# pwr.net
KiCad netlist of a schematic drawn in Altium Designer
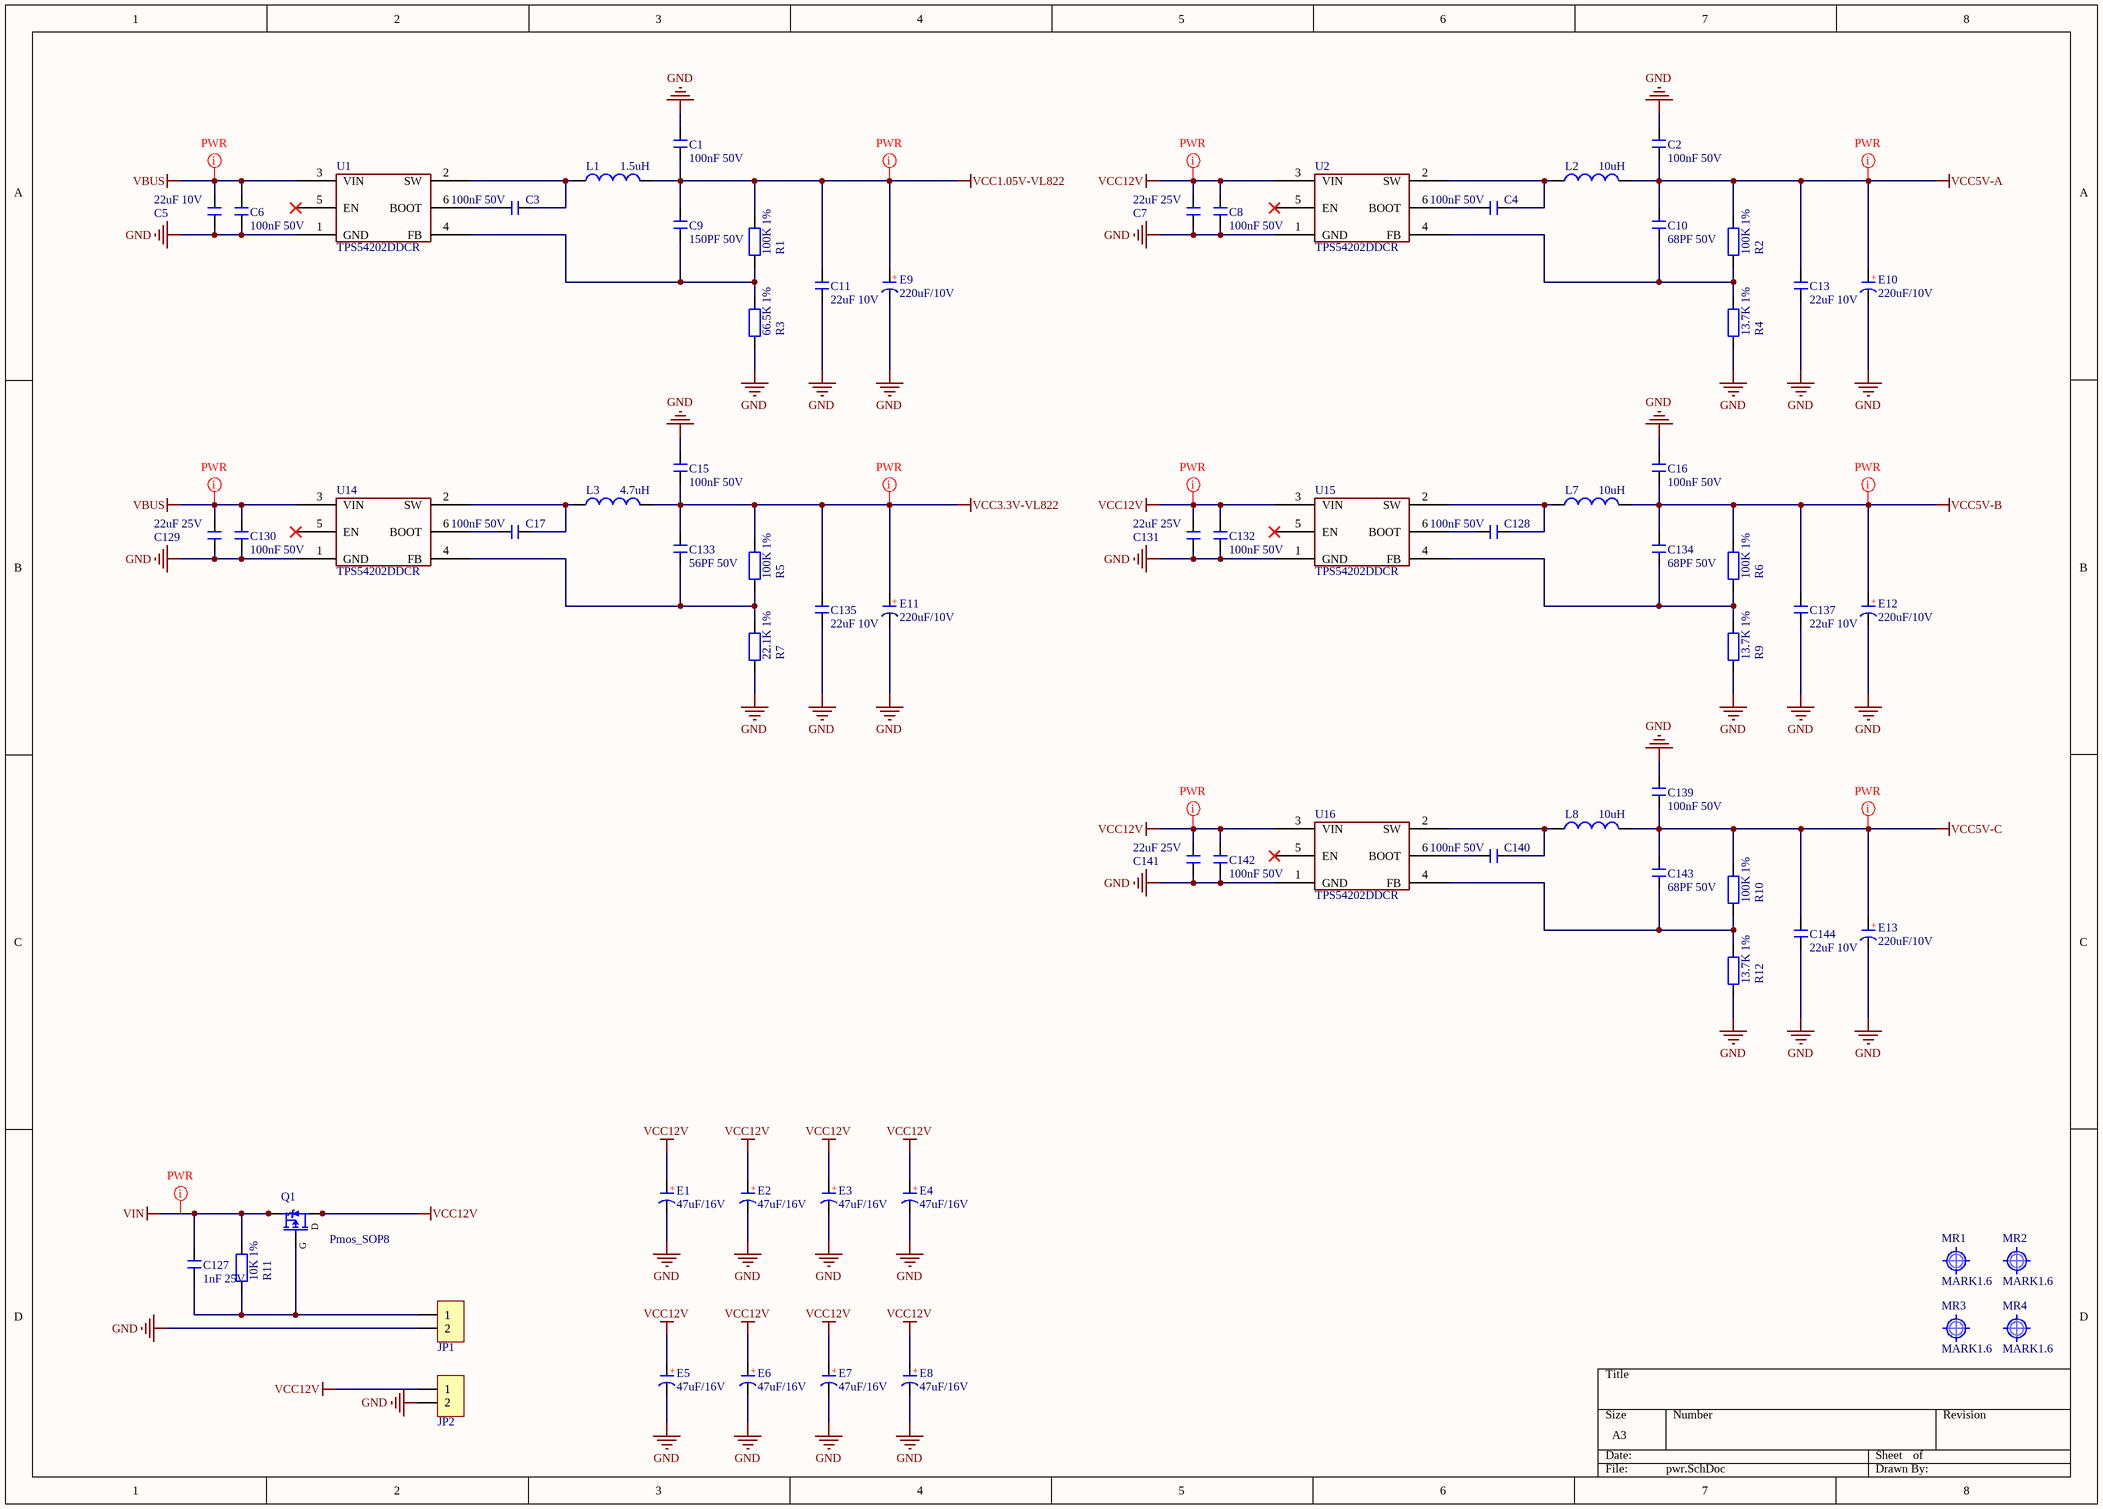
[diagram p0: pwr.SchDoc]

(export (version "E")
  (design (tool "Eeschema 10.0.6"))
  (components
    (comp (ref "C1")
      (value "100nF 50V")
      (footprint "C0402_L")
      (description "无极性贴片电容")
      (fields (field (name "版权归属") "源创客"))
      (libsource (lib "Capacitor") (part "C"))
    )
    (comp (ref "C2")
      (value "100nF 50V")
      (footprint "C0402_L")
      (description "无极性贴片电容")
      (fields (field (name "版权归属") "源创客"))
      (libsource (lib "Capacitor") (part "C"))
    )
    (comp (ref "C3")
      (value "100nF 50V")
      (footprint "C0402_L")
      (description "无极性贴片电容")
      (fields (field (name "版权归属") "源创客"))
      (libsource (lib "Capacitor") (part "C"))
    )
    (comp (ref "C4")
      (value "100nF 50V")
      (footprint "C0402_L")
      (description "无极性贴片电容")
      (fields (field (name "版权归属") "源创客"))
      (libsource (lib "Capacitor") (part "C"))
    )
    (comp (ref "C5")
      (value "22uF 10V")
      (footprint "C0805_L")
      (description "无极性贴片电容")
      (fields (field (name "版权归属") "源创客"))
      (libsource (lib "Capacitor") (part "C"))
    )
    (comp (ref "C6")
      (value "100nF 50V")
      (footprint "C0402_L")
      (description "无极性贴片电容")
      (fields (field (name "版权归属") "源创客"))
      (libsource (lib "Capacitor") (part "C"))
    )
    (comp (ref "C7")
      (value "22uF 25V")
      (footprint "C0805_L")
      (description "无极性贴片电容")
      (fields (field (name "版权归属") "源创客"))
      (libsource (lib "Capacitor") (part "C"))
    )
    (comp (ref "C8")
      (value "100nF 50V")
      (footprint "C0402_L")
      (description "无极性贴片电容")
      (fields (field (name "版权归属") "源创客"))
      (libsource (lib "Capacitor") (part "C"))
    )
    (comp (ref "C9")
      (value "150PF 50V")
      (footprint "C0402_L")
      (description "无极性贴片电容")
      (fields (field (name "版权归属") "源创客"))
      (libsource (lib "Capacitor") (part "C"))
    )
    (comp (ref "C10")
      (value "68PF 50V")
      (footprint "C0402_L")
      (description "无极性贴片电容")
      (fields (field (name "版权归属") "源创客"))
      (libsource (lib "Capacitor") (part "C"))
    )
    (comp (ref "C11")
      (value "22uF 10V")
      (footprint "C0603_L")
      (description "无极性贴片电容")
      (fields (field (name "版权归属") "源创客"))
      (libsource (lib "Capacitor") (part "C"))
    )
    (comp (ref "C13")
      (value "22uF 10V")
      (footprint "C0603_L")
      (description "无极性贴片电容")
      (fields (field (name "版权归属") "源创客"))
      (libsource (lib "Capacitor") (part "C"))
    )
    (comp (ref "C15")
      (value "100nF 50V")
      (footprint "C0402_L")
      (description "无极性贴片电容")
      (fields (field (name "版权归属") "源创客"))
      (libsource (lib "Capacitor") (part "C"))
    )
    (comp (ref "C16")
      (value "100nF 50V")
      (footprint "C0402_L")
      (description "无极性贴片电容")
      (fields (field (name "版权归属") "源创客"))
      (libsource (lib "Capacitor") (part "C"))
    )
    (comp (ref "C17")
      (value "100nF 50V")
      (footprint "C0402_L")
      (description "无极性贴片电容")
      (fields (field (name "版权归属") "源创客"))
      (libsource (lib "Capacitor") (part "C"))
    )
    (comp (ref "C127")
      (value "1nF 25V")
      (footprint "C0402_L")
      (description "无极性贴片电容")
      (fields (field (name "版权归属") "源创客"))
      (libsource (lib "Capacitor") (part "C"))
    )
    (comp (ref "C128")
      (value "100nF 50V")
      (footprint "C0402_L")
      (description "无极性贴片电容")
      (fields (field (name "版权归属") "源创客"))
      (libsource (lib "Capacitor") (part "C"))
    )
    (comp (ref "C129")
      (value "22uF 25V")
      (footprint "C0805_L")
      (description "无极性贴片电容")
      (fields (field (name "版权归属") "源创客"))
      (libsource (lib "Capacitor") (part "C"))
    )
    (comp (ref "C130")
      (value "100nF 50V")
      (footprint "C0402_L")
      (description "无极性贴片电容")
      (fields (field (name "版权归属") "源创客"))
      (libsource (lib "Capacitor") (part "C"))
    )
    (comp (ref "C131")
      (value "22uF 25V")
      (footprint "C0805_L")
      (description "无极性贴片电容")
      (fields (field (name "版权归属") "源创客"))
      (libsource (lib "Capacitor") (part "C"))
    )
    (comp (ref "C132")
      (value "100nF 50V")
      (footprint "C0402_L")
      (description "无极性贴片电容")
      (fields (field (name "版权归属") "源创客"))
      (libsource (lib "Capacitor") (part "C"))
    )
    (comp (ref "C133")
      (value "56PF 50V")
      (footprint "C0402_L")
      (description "无极性贴片电容")
      (fields (field (name "版权归属") "源创客"))
      (libsource (lib "Capacitor") (part "C"))
    )
    (comp (ref "C134")
      (value "68PF 50V")
      (footprint "C0402_L")
      (description "无极性贴片电容")
      (fields (field (name "版权归属") "源创客"))
      (libsource (lib "Capacitor") (part "C"))
    )
    (comp (ref "C135")
      (value "22uF 10V")
      (footprint "C0603_L")
      (description "无极性贴片电容")
      (fields (field (name "版权归属") "源创客"))
      (libsource (lib "Capacitor") (part "C"))
    )
    (comp (ref "C137")
      (value "22uF 10V")
      (footprint "C0603_L")
      (description "无极性贴片电容")
      (fields (field (name "版权归属") "源创客"))
      (libsource (lib "Capacitor") (part "C"))
    )
    (comp (ref "C139")
      (value "100nF 50V")
      (footprint "C0402_L")
      (description "无极性贴片电容")
      (fields (field (name "版权归属") "源创客"))
      (libsource (lib "Capacitor") (part "C"))
    )
    (comp (ref "C140")
      (value "100nF 50V")
      (footprint "C0402_L")
      (description "无极性贴片电容")
      (fields (field (name "版权归属") "源创客"))
      (libsource (lib "Capacitor") (part "C"))
    )
    (comp (ref "C141")
      (value "22uF 25V")
      (footprint "C0805_L")
      (description "无极性贴片电容")
      (fields (field (name "版权归属") "源创客"))
      (libsource (lib "Capacitor") (part "C"))
    )
    (comp (ref "C142")
      (value "100nF 50V")
      (footprint "C0402_L")
      (description "无极性贴片电容")
      (fields (field (name "版权归属") "源创客"))
      (libsource (lib "Capacitor") (part "C"))
    )
    (comp (ref "C143")
      (value "68PF 50V")
      (footprint "C0402_L")
      (description "无极性贴片电容")
      (fields (field (name "版权归属") "源创客"))
      (libsource (lib "Capacitor") (part "C"))
    )
    (comp (ref "C144")
      (value "22uF 10V")
      (footprint "C0603_L")
      (description "无极性贴片电容")
      (fields (field (name "版权归属") "源创客"))
      (libsource (lib "Capacitor") (part "C"))
    )
    (comp (ref "E1")
      (value "47uF/16V")
      (footprint "CS 6*4 - R")
      (description "贴片电解电容")
      (fields (field (name "版权归属") "源创客"))
      (libsource (lib "Capacitor") (part "C-CD"))
    )
    (comp (ref "E2")
      (value "47uF/16V")
      (footprint "CS 6*4 - R")
      (description "贴片电解电容")
      (fields (field (name "版权归属") "源创客"))
      (libsource (lib "Capacitor") (part "C-CD"))
    )
    (comp (ref "E3")
      (value "47uF/16V")
      (footprint "CS 6*4 - R")
      (description "贴片电解电容")
      (fields (field (name "版权归属") "源创客"))
      (libsource (lib "Capacitor") (part "C-CD"))
    )
    (comp (ref "E4")
      (value "47uF/16V")
      (footprint "CS 6*4 - R")
      (description "贴片电解电容")
      (fields (field (name "版权归属") "源创客"))
      (libsource (lib "Capacitor") (part "C-CD"))
    )
    (comp (ref "E5")
      (value "47uF/16V")
      (footprint "CS 6*4 - R")
      (description "贴片电解电容")
      (fields (field (name "版权归属") "源创客"))
      (libsource (lib "Capacitor") (part "C-CD"))
    )
    (comp (ref "E6")
      (value "47uF/16V")
      (footprint "CS 6*4 - R")
      (description "贴片电解电容")
      (fields (field (name "版权归属") "源创客"))
      (libsource (lib "Capacitor") (part "C-CD"))
    )
    (comp (ref "E7")
      (value "47uF/16V")
      (footprint "CS 6*4 - R")
      (description "贴片电解电容")
      (fields (field (name "版权归属") "源创客"))
      (libsource (lib "Capacitor") (part "C-CD"))
    )
    (comp (ref "E8")
      (value "47uF/16V")
      (footprint "CS 6*4 - R")
      (description "贴片电解电容")
      (fields (field (name "版权归属") "源创客"))
      (libsource (lib "Capacitor") (part "C-CD"))
    )
    (comp (ref "E9")
      (value "220uF/10V")
      (footprint "CS 6*4 - B")
      (description "贴片电解电容")
      (fields (field (name "版权归属") "源创客"))
      (libsource (lib "Capacitor") (part "C-CD"))
    )
    (comp (ref "E10")
      (value "220uF/10V")
      (footprint "CS 6*4 - B")
      (description "贴片电解电容")
      (fields (field (name "版权归属") "源创客"))
      (libsource (lib "Capacitor") (part "C-CD"))
    )
    (comp (ref "E11")
      (value "220uF/10V")
      (footprint "CS 6*4 - B")
      (description "贴片电解电容")
      (fields (field (name "版权归属") "源创客"))
      (libsource (lib "Capacitor") (part "C-CD"))
    )
    (comp (ref "E12")
      (value "220uF/10V")
      (footprint "CS 6*4 - B")
      (description "贴片电解电容")
      (fields (field (name "版权归属") "源创客"))
      (libsource (lib "Capacitor") (part "C-CD"))
    )
    (comp (ref "E13")
      (value "220uF/10V")
      (footprint "CS 6*4 - B")
      (description "贴片电解电容")
      (fields (field (name "版权归属") "源创客"))
      (libsource (lib "Capacitor") (part "C-CD"))
    )
    (comp (ref "JP1")
      (value "HDR-1X2")
      (footprint "ZH1.5-WS-2P")
      (description "2P接插件")
      (fields (field (name "版权归属") "源创客"))
      (libsource (lib "Connector-PinHeader") (part "Header 2"))
    )
    (comp (ref "JP2")
      (value "HDR-1X2")
      (footprint "XH2.54-WS-2P")
      (description "2P接插件")
      (fields (field (name "版权归属") "源创客"))
      (libsource (lib "Connector-PinHeader") (part "Header 2"))
    )
    (comp (ref "L1")
      (value "1.5uH")
      (footprint "SMMS0420")
      (description "小功率贴片电感")
      (fields (field (name "版权归属") "源创客"))
      (libsource (lib "Inductor") (part "L"))
    )
    (comp (ref "L2")
      (value "10uH")
      (footprint "SMMS0420")
      (description "小功率贴片电感")
      (fields (field (name "版权归属") "源创客"))
      (libsource (lib "Inductor") (part "L"))
    )
    (comp (ref "L3")
      (value "4.7uH")
      (footprint "SMMS0420")
      (description "小功率贴片电感")
      (fields (field (name "版权归属") "源创客"))
      (libsource (lib "Inductor") (part "L"))
    )
    (comp (ref "L7")
      (value "10uH")
      (footprint "SMMS0420")
      (description "小功率贴片电感")
      (fields (field (name "版权归属") "源创客"))
      (libsource (lib "Inductor") (part "L"))
    )
    (comp (ref "L8")
      (value "10uH")
      (footprint "SMMS0420")
      (description "小功率贴片电感")
      (fields (field (name "版权归属") "源创客"))
      (libsource (lib "Inductor") (part "L"))
    )
    (comp (ref "MR1")
      (value "MARK1.6")
      (footprint "Mark 1")
      (description "光学定位点")
      (fields (field (name "版权归属") "源创客"))
      (libsource (lib "Hole") (part "MARK"))
    )
    (comp (ref "MR2")
      (value "MARK1.6")
      (footprint "Mark 1")
      (description "光学定位点")
      (fields (field (name "版权归属") "源创客"))
      (libsource (lib "Hole") (part "MARK"))
    )
    (comp (ref "MR3")
      (value "MARK1.6")
      (footprint "Mark 1")
      (description "光学定位点")
      (fields (field (name "版权归属") "源创客"))
      (libsource (lib "Hole") (part "MARK"))
    )
    (comp (ref "MR4")
      (value "MARK1.6")
      (footprint "Mark 1")
      (description "光学定位点")
      (fields (field (name "版权归属") "源创客"))
      (libsource (lib "Hole") (part "MARK"))
    )
    (comp (ref "Q1")
      (value "Pmos_SOP8")
      (footprint "SOP8_L")
      (fields (field (name "版权归属") "源创客"))
      (libsource (lib "MOSFET BJT IGBT") (part "Pmos_SOP8"))
    )
    (comp (ref "R1")
      (value "100K 1%")
      (footprint "R0402_L")
      (description "贴片电阻")
      (fields (field (name "版权归属") "源创客"))
      (libsource (lib "Resistor") (part "R"))
    )
    (comp (ref "R2")
      (value "100K 1%")
      (footprint "R0402_L")
      (description "贴片电阻")
      (fields (field (name "版权归属") "源创客"))
      (libsource (lib "Resistor") (part "R"))
    )
    (comp (ref "R3")
      (value "66.5K 1%")
      (footprint "R0402_L")
      (description "贴片电阻")
      (fields (field (name "版权归属") "源创客"))
      (libsource (lib "Resistor") (part "R"))
    )
    (comp (ref "R4")
      (value "13.7K 1%")
      (footprint "R0402_L")
      (description "贴片电阻")
      (fields (field (name "版权归属") "源创客"))
      (libsource (lib "Resistor") (part "R"))
    )
    (comp (ref "R5")
      (value "100K 1%")
      (footprint "R0402_L")
      (description "贴片电阻")
      (fields (field (name "版权归属") "源创客"))
      (libsource (lib "Resistor") (part "R"))
    )
    (comp (ref "R6")
      (value "100K 1%")
      (footprint "R0402_L")
      (description "贴片电阻")
      (fields (field (name "版权归属") "源创客"))
      (libsource (lib "Resistor") (part "R"))
    )
    (comp (ref "R7")
      (value "22.1K 1%")
      (footprint "R0402_L")
      (description "贴片电阻")
      (fields (field (name "版权归属") "源创客"))
      (libsource (lib "Resistor") (part "R"))
    )
    (comp (ref "R9")
      (value "13.7K 1%")
      (footprint "R0402_L")
      (description "贴片电阻")
      (fields (field (name "版权归属") "源创客"))
      (libsource (lib "Resistor") (part "R"))
    )
    (comp (ref "R10")
      (value "100K 1%")
      (footprint "R0402_L")
      (description "贴片电阻")
      (fields (field (name "版权归属") "源创客"))
      (libsource (lib "Resistor") (part "R"))
    )
    (comp (ref "R11")
      (value "10K 1%")
      (footprint "R0402_L")
      (description "贴片电阻")
      (fields (field (name "版权归属") "源创客"))
      (libsource (lib "Resistor") (part "R"))
    )
    (comp (ref "R12")
      (value "13.7K 1%")
      (footprint "R0402_L")
      (description "贴片电阻")
      (fields (field (name "版权归属") "源创客"))
      (libsource (lib "Resistor") (part "R"))
    )
    (comp (ref "U1")
      (value "TPS54202DDCR")
      (footprint "SOT23-6L")
      (description "DCDC Convert")
      (libsource (lib "DCDC Convert") (part "TPS54202DDCR"))
    )
    (comp (ref "U2")
      (value "TPS54202DDCR")
      (footprint "SOT23-6L")
      (description "DCDC Convert")
      (libsource (lib "DCDC Convert") (part "TPS54202DDCR"))
    )
    (comp (ref "U14")
      (value "TPS54202DDCR")
      (footprint "SOT23-6L")
      (description "DCDC Convert")
      (libsource (lib "DCDC Convert") (part "TPS54202DDCR"))
    )
    (comp (ref "U15")
      (value "TPS54202DDCR")
      (footprint "SOT23-6L")
      (description "DCDC Convert")
      (libsource (lib "DCDC Convert") (part "TPS54202DDCR"))
    )
    (comp (ref "U16")
      (value "TPS54202DDCR")
      (footprint "SOT23-6L")
      (description "DCDC Convert")
      (libsource (lib "DCDC Convert") (part "TPS54202DDCR"))
    )
  )
  (nets
    (net (code "1") (name "GND") (class "Default")
      (node (ref "C1") (pin "2") (pinfunction "2_2") (pintype "passive"))
      (node (ref "C11") (pin "2") (pinfunction "2_2") (pintype "passive"))
      (node (ref "C129") (pin "1") (pinfunction "1_1") (pintype "passive"))
      (node (ref "C13") (pin "2") (pinfunction "2_2") (pintype "passive"))
      (node (ref "C130") (pin "1") (pinfunction "1_1") (pintype "passive"))
      (node (ref "C131") (pin "1") (pinfunction "1_1") (pintype "passive"))
      (node (ref "C132") (pin "1") (pinfunction "1_1") (pintype "passive"))
      (node (ref "C135") (pin "2") (pinfunction "2_2") (pintype "passive"))
      (node (ref "C137") (pin "2") (pinfunction "2_2") (pintype "passive"))
      (node (ref "C139") (pin "2") (pinfunction "2_2") (pintype "passive"))
      (node (ref "C141") (pin "1") (pinfunction "1_1") (pintype "passive"))
      (node (ref "C142") (pin "1") (pinfunction "1_1") (pintype "passive"))
      (node (ref "C144") (pin "2") (pinfunction "2_2") (pintype "passive"))
      (node (ref "C15") (pin "2") (pinfunction "2_2") (pintype "passive"))
      (node (ref "C16") (pin "2") (pinfunction "2_2") (pintype "passive"))
      (node (ref "C2") (pin "2") (pinfunction "2_2") (pintype "passive"))
      (node (ref "C5") (pin "1") (pinfunction "1_1") (pintype "passive"))
      (node (ref "C6") (pin "1") (pinfunction "1_1") (pintype "passive"))
      (node (ref "C7") (pin "1") (pinfunction "1_1") (pintype "passive"))
      (node (ref "C8") (pin "1") (pinfunction "1_1") (pintype "passive"))
      (node (ref "E1") (pin "2") (pinfunction "K_2") (pintype "passive"))
      (node (ref "E10") (pin "2") (pinfunction "K_2") (pintype "passive"))
      (node (ref "E11") (pin "2") (pinfunction "K_2") (pintype "passive"))
      (node (ref "E12") (pin "2") (pinfunction "K_2") (pintype "passive"))
      (node (ref "E13") (pin "2") (pinfunction "K_2") (pintype "passive"))
      (node (ref "E2") (pin "2") (pinfunction "K_2") (pintype "passive"))
      (node (ref "E3") (pin "2") (pinfunction "K_2") (pintype "passive"))
      (node (ref "E4") (pin "2") (pinfunction "K_2") (pintype "passive"))
      (node (ref "E5") (pin "2") (pinfunction "K_2") (pintype "passive"))
      (node (ref "E6") (pin "2") (pinfunction "K_2") (pintype "passive"))
      (node (ref "E7") (pin "2") (pinfunction "K_2") (pintype "passive"))
      (node (ref "E8") (pin "2") (pinfunction "K_2") (pintype "passive"))
      (node (ref "E9") (pin "2") (pinfunction "K_2") (pintype "passive"))
      (node (ref "JP1") (pin "2") (pinfunction "2_2") (pintype "passive"))
      (node (ref "JP2") (pin "2") (pinfunction "2_2") (pintype "passive"))
      (node (ref "R12") (pin "2") (pinfunction "2_2") (pintype "passive"))
      (node (ref "R3") (pin "2") (pinfunction "2_2") (pintype "passive"))
      (node (ref "R4") (pin "2") (pinfunction "2_2") (pintype "passive"))
      (node (ref "R7") (pin "2") (pinfunction "2_2") (pintype "passive"))
      (node (ref "R9") (pin "2") (pinfunction "2_2") (pintype "passive"))
      (node (ref "U1") (pin "1") (pinfunction "GND_1") (pintype "passive"))
      (node (ref "U14") (pin "1") (pinfunction "GND_1") (pintype "passive"))
      (node (ref "U15") (pin "1") (pinfunction "GND_1") (pintype "passive"))
      (node (ref "U16") (pin "1") (pinfunction "GND_1") (pintype "passive"))
      (node (ref "U2") (pin "1") (pinfunction "GND_1") (pintype "passive"))
    )
    (net (code "2") (name "Net-(Q1-G)") (class "Default")
      (node (ref "C127") (pin "2") (pinfunction "2_2") (pintype "passive"))
      (node (ref "JP1") (pin "1") (pinfunction "1_1") (pintype "passive"))
      (node (ref "Q1") (pin "4") (pinfunction "G_4") (pintype "passive"))
      (node (ref "R11") (pin "2") (pinfunction "2_2") (pintype "passive"))
    )
    (net (code "3") (name "Net-(U1-BOOT)") (class "Default")
      (node (ref "C3") (pin "1") (pinfunction "1_1") (pintype "passive"))
      (node (ref "U1") (pin "6") (pinfunction "BOOT_6") (pintype "passive"))
    )
    (net (code "4") (name "Net-(U1-FB)") (class "Default")
      (node (ref "C9") (pin "1") (pinfunction "1_1") (pintype "passive"))
      (node (ref "R1") (pin "2") (pinfunction "2_2") (pintype "passive"))
      (node (ref "R3") (pin "1") (pinfunction "1_1") (pintype "passive"))
      (node (ref "U1") (pin "4") (pinfunction "FB_4") (pintype "passive"))
    )
    (net (code "5") (name "Net-(U1-SW)") (class "Default")
      (node (ref "C3") (pin "2") (pinfunction "2_2") (pintype "passive"))
      (node (ref "L1") (pin "1") (pinfunction "1_1") (pintype "passive"))
      (node (ref "U1") (pin "2") (pinfunction "SW_2") (pintype "passive"))
    )
    (net (code "6") (name "Net-(U2-BOOT)") (class "Default")
      (node (ref "C4") (pin "1") (pinfunction "1_1") (pintype "passive"))
      (node (ref "U2") (pin "6") (pinfunction "BOOT_6") (pintype "passive"))
    )
    (net (code "7") (name "Net-(U2-FB)") (class "Default")
      (node (ref "C10") (pin "1") (pinfunction "1_1") (pintype "passive"))
      (node (ref "R2") (pin "2") (pinfunction "2_2") (pintype "passive"))
      (node (ref "R4") (pin "1") (pinfunction "1_1") (pintype "passive"))
      (node (ref "U2") (pin "4") (pinfunction "FB_4") (pintype "passive"))
    )
    (net (code "8") (name "Net-(U2-SW)") (class "Default")
      (node (ref "C4") (pin "2") (pinfunction "2_2") (pintype "passive"))
      (node (ref "L2") (pin "1") (pinfunction "1_1") (pintype "passive"))
      (node (ref "U2") (pin "2") (pinfunction "SW_2") (pintype "passive"))
    )
    (net (code "9") (name "Net-(U14-BOOT)") (class "Default")
      (node (ref "C17") (pin "1") (pinfunction "1_1") (pintype "passive"))
      (node (ref "U14") (pin "6") (pinfunction "BOOT_6") (pintype "passive"))
    )
    (net (code "10") (name "Net-(U14-FB)") (class "Default")
      (node (ref "C133") (pin "1") (pinfunction "1_1") (pintype "passive"))
      (node (ref "R5") (pin "2") (pinfunction "2_2") (pintype "passive"))
      (node (ref "R7") (pin "1") (pinfunction "1_1") (pintype "passive"))
      (node (ref "U14") (pin "4") (pinfunction "FB_4") (pintype "passive"))
    )
    (net (code "11") (name "Net-(U14-SW)") (class "Default")
      (node (ref "C17") (pin "2") (pinfunction "2_2") (pintype "passive"))
      (node (ref "L3") (pin "1") (pinfunction "1_1") (pintype "passive"))
      (node (ref "U14") (pin "2") (pinfunction "SW_2") (pintype "passive"))
    )
    (net (code "12") (name "Net-(U15-BOOT)") (class "Default")
      (node (ref "C128") (pin "1") (pinfunction "1_1") (pintype "passive"))
      (node (ref "U15") (pin "6") (pinfunction "BOOT_6") (pintype "passive"))
    )
    (net (code "13") (name "Net-(U15-FB)") (class "Default")
      (node (ref "C134") (pin "1") (pinfunction "1_1") (pintype "passive"))
      (node (ref "R6") (pin "2") (pinfunction "2_2") (pintype "passive"))
      (node (ref "R9") (pin "1") (pinfunction "1_1") (pintype "passive"))
      (node (ref "U15") (pin "4") (pinfunction "FB_4") (pintype "passive"))
    )
    (net (code "14") (name "Net-(U15-SW)") (class "Default")
      (node (ref "C128") (pin "2") (pinfunction "2_2") (pintype "passive"))
      (node (ref "L7") (pin "1") (pinfunction "1_1") (pintype "passive"))
      (node (ref "U15") (pin "2") (pinfunction "SW_2") (pintype "passive"))
    )
    (net (code "15") (name "Net-(U16-BOOT)") (class "Default")
      (node (ref "C140") (pin "1") (pinfunction "1_1") (pintype "passive"))
      (node (ref "U16") (pin "6") (pinfunction "BOOT_6") (pintype "passive"))
    )
    (net (code "16") (name "Net-(U16-FB)") (class "Default")
      (node (ref "C143") (pin "1") (pinfunction "1_1") (pintype "passive"))
      (node (ref "R10") (pin "2") (pinfunction "2_2") (pintype "passive"))
      (node (ref "R12") (pin "1") (pinfunction "1_1") (pintype "passive"))
      (node (ref "U16") (pin "4") (pinfunction "FB_4") (pintype "passive"))
    )
    (net (code "17") (name "Net-(U16-SW)") (class "Default")
      (node (ref "C140") (pin "2") (pinfunction "2_2") (pintype "passive"))
      (node (ref "L8") (pin "1") (pinfunction "1_1") (pintype "passive"))
      (node (ref "U16") (pin "2") (pinfunction "SW_2") (pintype "passive"))
    )
    (net (code "18") (name "VBUS") (class "Default")
      (node (ref "C129") (pin "2") (pinfunction "2_2") (pintype "passive"))
      (node (ref "C130") (pin "2") (pinfunction "2_2") (pintype "passive"))
      (node (ref "C5") (pin "2") (pinfunction "2_2") (pintype "passive"))
      (node (ref "C6") (pin "2") (pinfunction "2_2") (pintype "passive"))
      (node (ref "U1") (pin "3") (pinfunction "VIN_3") (pintype "passive"))
      (node (ref "U14") (pin "3") (pinfunction "VIN_3") (pintype "passive"))
    )
    (net (code "19") (name "VCC1.05V-VL822") (class "Default")
      (node (ref "C1") (pin "1") (pinfunction "1_1") (pintype "passive"))
      (node (ref "C11") (pin "1") (pinfunction "1_1") (pintype "passive"))
      (node (ref "C9") (pin "2") (pinfunction "2_2") (pintype "passive"))
      (node (ref "E9") (pin "1") (pinfunction "A_1") (pintype "passive"))
      (node (ref "L1") (pin "2") (pinfunction "2_2") (pintype "passive"))
      (node (ref "R1") (pin "1") (pinfunction "1_1") (pintype "passive"))
    )
    (net (code "20") (name "VCC3.3V-VL822") (class "Default")
      (node (ref "C133") (pin "2") (pinfunction "2_2") (pintype "passive"))
      (node (ref "C135") (pin "1") (pinfunction "1_1") (pintype "passive"))
      (node (ref "C15") (pin "1") (pinfunction "1_1") (pintype "passive"))
      (node (ref "E11") (pin "1") (pinfunction "A_1") (pintype "passive"))
      (node (ref "L3") (pin "2") (pinfunction "2_2") (pintype "passive"))
      (node (ref "R5") (pin "1") (pinfunction "1_1") (pintype "passive"))
    )
    (net (code "21") (name "VCC5V-A") (class "Default")
      (node (ref "C10") (pin "2") (pinfunction "2_2") (pintype "passive"))
      (node (ref "C13") (pin "1") (pinfunction "1_1") (pintype "passive"))
      (node (ref "C2") (pin "1") (pinfunction "1_1") (pintype "passive"))
      (node (ref "E10") (pin "1") (pinfunction "A_1") (pintype "passive"))
      (node (ref "L2") (pin "2") (pinfunction "2_2") (pintype "passive"))
      (node (ref "R2") (pin "1") (pinfunction "1_1") (pintype "passive"))
    )
    (net (code "22") (name "VCC5V-B") (class "Default")
      (node (ref "C134") (pin "2") (pinfunction "2_2") (pintype "passive"))
      (node (ref "C137") (pin "1") (pinfunction "1_1") (pintype "passive"))
      (node (ref "C16") (pin "1") (pinfunction "1_1") (pintype "passive"))
      (node (ref "E12") (pin "1") (pinfunction "A_1") (pintype "passive"))
      (node (ref "L7") (pin "2") (pinfunction "2_2") (pintype "passive"))
      (node (ref "R6") (pin "1") (pinfunction "1_1") (pintype "passive"))
    )
    (net (code "23") (name "VCC5V-C") (class "Default")
      (node (ref "C139") (pin "1") (pinfunction "1_1") (pintype "passive"))
      (node (ref "C143") (pin "2") (pinfunction "2_2") (pintype "passive"))
      (node (ref "C144") (pin "1") (pinfunction "1_1") (pintype "passive"))
      (node (ref "E13") (pin "1") (pinfunction "A_1") (pintype "passive"))
      (node (ref "L8") (pin "2") (pinfunction "2_2") (pintype "passive"))
      (node (ref "R10") (pin "1") (pinfunction "1_1") (pintype "passive"))
    )
    (net (code "24") (name "VCC12V") (class "Default")
      (node (ref "C131") (pin "2") (pinfunction "2_2") (pintype "passive"))
      (node (ref "C132") (pin "2") (pinfunction "2_2") (pintype "passive"))
      (node (ref "C141") (pin "2") (pinfunction "2_2") (pintype "passive"))
      (node (ref "C142") (pin "2") (pinfunction "2_2") (pintype "passive"))
      (node (ref "C7") (pin "2") (pinfunction "2_2") (pintype "passive"))
      (node (ref "C8") (pin "2") (pinfunction "2_2") (pintype "passive"))
      (node (ref "E1") (pin "1") (pinfunction "A_1") (pintype "passive"))
      (node (ref "E2") (pin "1") (pinfunction "A_1") (pintype "passive"))
      (node (ref "E3") (pin "1") (pinfunction "A_1") (pintype "passive"))
      (node (ref "E4") (pin "1") (pinfunction "A_1") (pintype "passive"))
      (node (ref "E5") (pin "1") (pinfunction "A_1") (pintype "passive"))
      (node (ref "E6") (pin "1") (pinfunction "A_1") (pintype "passive"))
      (node (ref "E7") (pin "1") (pinfunction "A_1") (pintype "passive"))
      (node (ref "E8") (pin "1") (pinfunction "A_1") (pintype "passive"))
      (node (ref "JP2") (pin "1") (pinfunction "1_1") (pintype "passive"))
      (node (ref "Q1") (pin "5") (pinfunction "D_5") (pintype "passive"))
      (node (ref "Q1") (pin "6") (pinfunction "D_6") (pintype "passive"))
      (node (ref "Q1") (pin "7") (pinfunction "D_7") (pintype "passive"))
      (node (ref "Q1") (pin "8") (pinfunction "D_8") (pintype "passive"))
      (node (ref "U15") (pin "3") (pinfunction "VIN_3") (pintype "passive"))
      (node (ref "U16") (pin "3") (pinfunction "VIN_3") (pintype "passive"))
      (node (ref "U2") (pin "3") (pinfunction "VIN_3") (pintype "passive"))
    )
    (net (code "25") (name "VIN") (class "Default")
      (node (ref "C127") (pin "1") (pinfunction "1_1") (pintype "passive"))
      (node (ref "Q1") (pin "1") (pinfunction "S_1") (pintype "passive"))
      (node (ref "Q1") (pin "2") (pinfunction "S_2") (pintype "passive"))
      (node (ref "Q1") (pin "3") (pinfunction "S_3") (pintype "passive"))
      (node (ref "R11") (pin "1") (pinfunction "1_1") (pintype "passive"))
    )
    (net (code "26") (name "unconnected-(U1-EN-Pad5)") (class "Default")
      (node (ref "U1") (pin "5") (pinfunction "EN_5") (pintype "passive+no_connect"))
    )
    (net (code "27") (name "unconnected-(U2-EN-Pad5)") (class "Default")
      (node (ref "U2") (pin "5") (pinfunction "EN_5") (pintype "passive+no_connect"))
    )
    (net (code "28") (name "unconnected-(U14-EN-Pad5)") (class "Default")
      (node (ref "U14") (pin "5") (pinfunction "EN_5") (pintype "passive+no_connect"))
    )
    (net (code "29") (name "unconnected-(U15-EN-Pad5)") (class "Default")
      (node (ref "U15") (pin "5") (pinfunction "EN_5") (pintype "passive+no_connect"))
    )
    (net (code "30") (name "unconnected-(U16-EN-Pad5)") (class "Default")
      (node (ref "U16") (pin "5") (pinfunction "EN_5") (pintype "passive+no_connect"))
    )
  )
)
